# SAMV71_Xplained_Ultra_Ethernet.net
KiCad netlist of a schematic drawn in Altium Designer
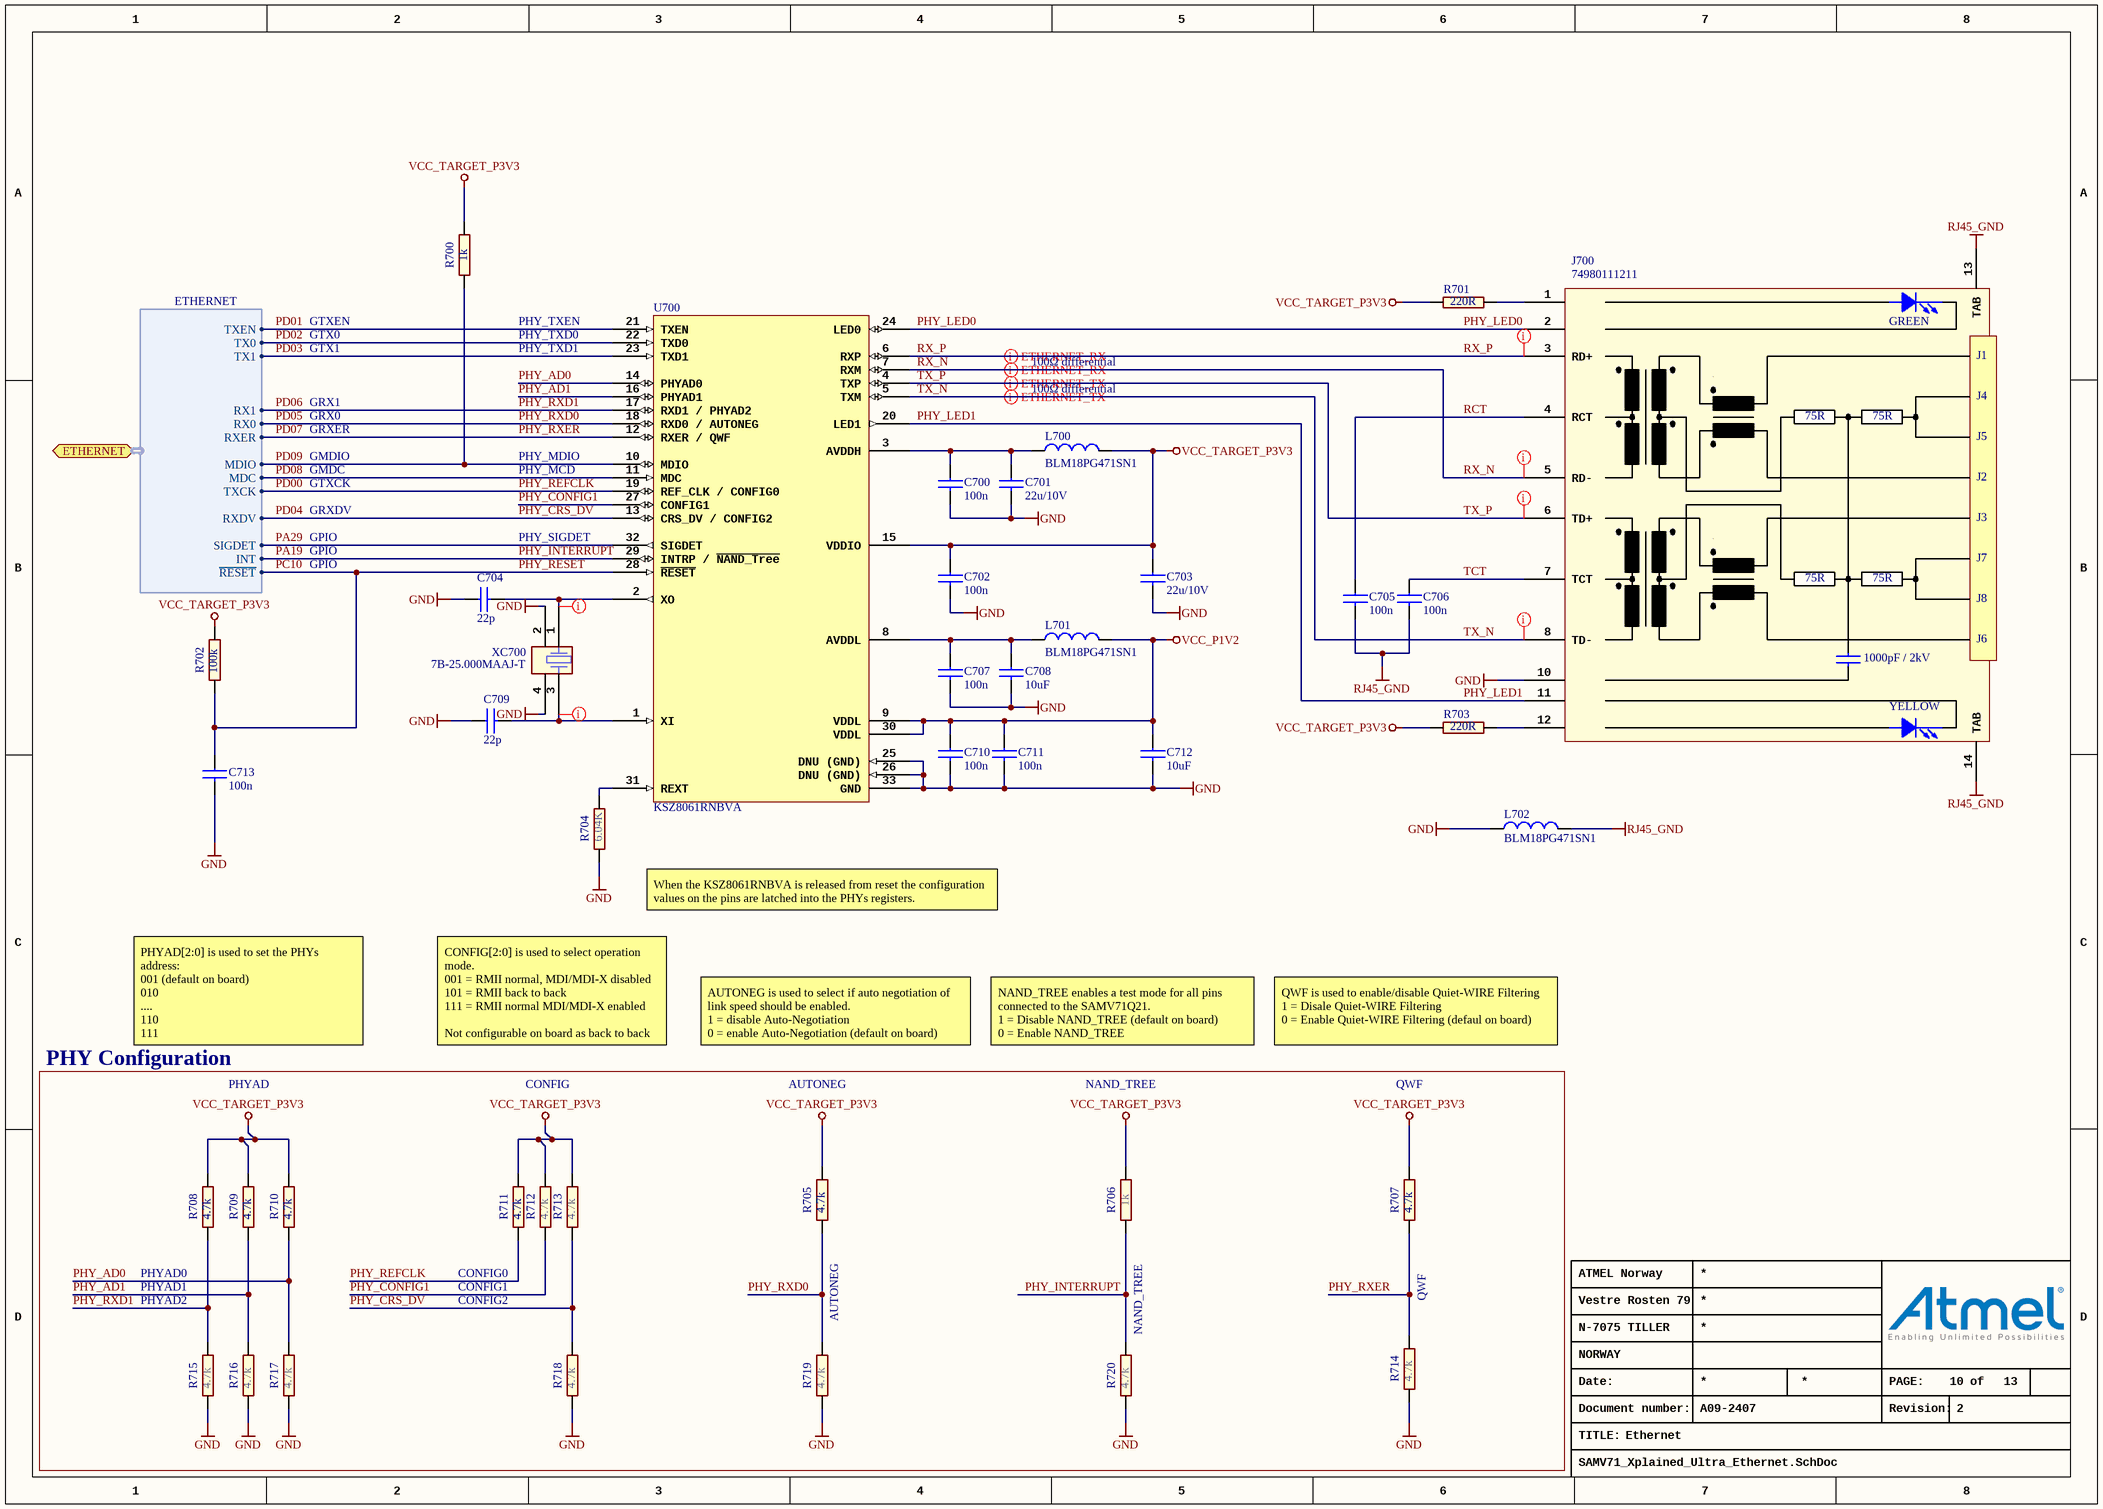
[diagram p0: SAMV71_Xplained_Ultra_Ethernet.SchDoc]

(export (version "E")
  (design (tool "Eeschema 10.0.6"))
  (components
    (comp (ref "C700")
      (value "100n")
      (footprint "AP1-00001")
      (description "Ceramic capacitor, SMD 0402, X7R, 16V, +/-10%")
      (fields (field (name "TOLERANCE") "16V, +/-10%") (field (name "MANUFACTURER") "Kemet"))
      (libsource (lib "AltiumDbLib") (part "CAP-NONPOL"))
    )
    (comp (ref "C701")
      (value "22u/10V")
      (footprint "AP1-00003")
      (description "Ceramic capacitor, SMD 0805, X5R, 10V, ±20%")
      (fields (field (name "MANUFACTURER") "tdk") (field (name "MPN") "C2012X5R1A226M/0.85"))
      (libsource (lib "AltiumDbLib") (part "CAP-NONPOL"))
    )
    (comp (ref "C702")
      (value "100n")
      (footprint "AP1-00001")
      (description "Ceramic capacitor, SMD 0402, X7R, 16V, +/-10%")
      (fields (field (name "TOLERANCE") "16V, +/-10%") (field (name "MANUFACTURER") "Kemet"))
      (libsource (lib "AltiumDbLib") (part "CAP-NONPOL"))
    )
    (comp (ref "C703")
      (value "22u/10V")
      (footprint "AP1-00003")
      (description "Ceramic capacitor, SMD 0805, X5R, 10V, ±20%")
      (fields (field (name "MANUFACTURER") "tdk") (field (name "MPN") "C2012X5R1A226M/0.85"))
      (libsource (lib "AltiumDbLib") (part "CAP-NONPOL"))
    )
    (comp (ref "C704")
      (value "22p")
      (footprint "AP1-00001")
      (description "Ceramic capacitor, SMD 0402, NP0, 50V, +/-5%")
      (fields (field (name "TOLERANCE") "50V, +/-5%") (field (name "Comment") "CAP-NONPOL"))
      (libsource (lib "AltiumDbLib") (part "CAP-NONPOL"))
    )
    (comp (ref "C705")
      (value "100n")
      (footprint "AP1-00001")
      (description "Ceramic capacitor, SMD 0402, X7R, 16V, +/-10%")
      (fields (field (name "TOLERANCE") "16V, +/-10%") (field (name "MANUFACTURER") "Kemet"))
      (libsource (lib "AltiumDbLib") (part "CAP-NONPOL"))
    )
    (comp (ref "C706")
      (value "100n")
      (footprint "AP1-00001")
      (description "Ceramic capacitor, SMD 0402, X7R, 16V, +/-10%")
      (fields (field (name "TOLERANCE") "16V, +/-10%") (field (name "MANUFACTURER") "Kemet"))
      (libsource (lib "AltiumDbLib") (part "CAP-NONPOL"))
    )
    (comp (ref "C707")
      (value "100n")
      (footprint "AP1-00001")
      (description "Ceramic capacitor, SMD 0402, X7R, 16V, +/-10%")
      (fields (field (name "TOLERANCE") "16V, +/-10%") (field (name "MANUFACTURER") "Kemet"))
      (libsource (lib "AltiumDbLib") (part "CAP-NONPOL"))
    )
    (comp (ref "C708")
      (value "10uF")
      (footprint "AP1-00041")
      (description "Ceramic capacitor, SMD 0805, X7R, 10V, 10 %, (de19441)")
      (fields (field (name "TOLERANCE") "10%") (field (name "MANUFACTURER") "Murata"))
      (libsource (lib "AltiumDbLib") (part "CAP-NONPOL"))
    )
    (comp (ref "C709")
      (value "22p")
      (footprint "AP1-00001")
      (description "Ceramic capacitor, SMD 0402, NP0, 50V, +/-5%")
      (fields (field (name "TOLERANCE") "50V, +/-5%") (field (name "Comment") "CAP-NONPOL"))
      (libsource (lib "AltiumDbLib") (part "CAP-NONPOL"))
    )
    (comp (ref "C710")
      (value "100n")
      (footprint "AP1-00001")
      (description "Ceramic capacitor, SMD 0402, X7R, 16V, +/-10%")
      (fields (field (name "TOLERANCE") "16V, +/-10%") (field (name "MANUFACTURER") "Kemet"))
      (libsource (lib "AltiumDbLib") (part "CAP-NONPOL"))
    )
    (comp (ref "C711")
      (value "100n")
      (footprint "AP1-00001")
      (description "Ceramic capacitor, SMD 0402, X7R, 16V, +/-10%")
      (fields (field (name "TOLERANCE") "16V, +/-10%") (field (name "MANUFACTURER") "Kemet"))
      (libsource (lib "AltiumDbLib") (part "CAP-NONPOL"))
    )
    (comp (ref "C712")
      (value "10uF")
      (footprint "AP1-00041")
      (description "Ceramic capacitor, SMD 0805, X7R, 10V, 10 %, (de19441)")
      (fields (field (name "TOLERANCE") "10%") (field (name "MANUFACTURER") "Murata"))
      (libsource (lib "AltiumDbLib") (part "CAP-NONPOL"))
    )
    (comp (ref "C713")
      (value "100n")
      (footprint "AP1-00001")
      (description "Ceramic capacitor, SMD 0402, X7R, 16V, +/-10%")
      (fields (field (name "TOLERANCE") "16V, +/-10%") (field (name "MANUFACTURER") "Kemet"))
      (libsource (lib "AltiumDbLib") (part "CAP-NONPOL"))
    )
    (comp (ref "J700")
      (value "74980111211")
      (footprint "AP8-00749")
      (description "10/100Base-TX, SMD, RJ45, green and yellow LEDs, integrated magnetics")
      (fields (field (name "MANUFACTURER") "Würth Elektronik") (field (name "Comment") "RJ45"))
      (libsource (lib "AltiumDbLib") (part "74980111211"))
    )
    (comp (ref "L700")
      (value "BLM18PG471SN1")
      (footprint "AP3-00005")
      (description "SMD RF inductor 0603. Z=470Ohm (@100MHz), Max R(dc)=0.65Ohm, Max current=1A")
      (fields (field (name "TOLERANCE") "±25%") (field (name "MANUFACTURER") "Murata"))
      (libsource (lib "AltiumDbLib") (part "INDUCTOR"))
    )
    (comp (ref "L701")
      (value "BLM18PG471SN1")
      (footprint "AP3-00005")
      (description "SMD RF inductor 0603. Z=470Ohm (@100MHz), Max R(dc)=0.65Ohm, Max current=1A")
      (fields (field (name "TOLERANCE") "±25%") (field (name "MANUFACTURER") "Murata"))
      (libsource (lib "AltiumDbLib") (part "INDUCTOR"))
    )
    (comp (ref "L702")
      (value "BLM18PG471SN1")
      (footprint "AP3-00005")
      (description "SMD RF inductor 0603. Z=470Ohm (@100MHz), Max R(dc)=0.65Ohm, Max current=1A")
      (fields (field (name "TOLERANCE") "±25%") (field (name "MANUFACTURER") "Murata"))
      (libsource (lib "") (part "INDUCTOR_1"))
    )
    (comp (ref "R700")
      (value "1k")
      (footprint "AP2-00000")
      (description "Thick film resistor, SMD 0402, 1/16W, 1%")
      (fields (field (name "TOLERANCE") "1 %") (field (name "Comment") "R2"))
      (libsource (lib "AltiumDbLib") (part "R2"))
    )
    (comp (ref "R701")
      (value "220R")
      (footprint "AP2-00000")
      (description "Thick film resistor, SMD 0402, 1/16W, 1%")
      (fields (field (name "TOLERANCE") "1 %") (field (name "Comment") "R2"))
      (libsource (lib "") (part "R2_3"))
    )
    (comp (ref "R702")
      (value "100k")
      (footprint "AP2-00000")
      (description "Thick film resistor, SMD 0402, 1/16W, 1%")
      (fields (field (name "TOLERANCE") "1 %") (field (name "Comment") "R2"))
      (libsource (lib "AltiumDbLib") (part "R2"))
    )
    (comp (ref "R703")
      (value "220R")
      (footprint "AP2-00000")
      (description "Thick film resistor, SMD 0402, 1/16W, 1%")
      (fields (field (name "TOLERANCE") "1 %") (field (name "Comment") "R2"))
      (libsource (lib "") (part "R2_1"))
    )
    (comp (ref "R704")
      (value "6.04K")
      (footprint "AP2-00000")
      (description "Thick film resistor, SMD 0402, 1/16W, 1%, E192")
      (fields (field (name "TOLERANCE") "1%") (field (name "Comment") "R2"))
      (libsource (lib "AltiumDbLib") (part "R2"))
    )
    (comp (ref "R705")
      (value "4.7k")
      (footprint "AP2-00000")
      (description "Thick film resistor, SMD 0402, 1/16W, 1%")
      (fields (field (name "TOLERANCE") "1 %") (field (name "Comment") "R2"))
      (libsource (lib "AltiumDbLib") (part "R2"))
    )
    (comp (ref "R706")
      (value "1k")
      (footprint "AP2-00000")
      (description "Thick film resistor, SMD 0402, 1/16W, 1%")
      (fields (field (name "TOLERANCE") "1 %") (field (name "Comment") "R2"))
      (libsource (lib "AltiumDbLib") (part "R2"))
    )
    (comp (ref "R707")
      (value "4.7k")
      (footprint "AP2-00000")
      (description "Thick film resistor, SMD 0402, 1/16W, 1%")
      (fields (field (name "TOLERANCE") "1 %") (field (name "Comment") "R2"))
      (libsource (lib "AltiumDbLib") (part "R2"))
    )
    (comp (ref "R708")
      (value "4.7k")
      (footprint "AP2-00000")
      (description "Thick film resistor, SMD 0402, 1/16W, 1%")
      (fields (field (name "TOLERANCE") "1 %") (field (name "Comment") "R2"))
      (libsource (lib "AltiumDbLib") (part "R2"))
    )
    (comp (ref "R709")
      (value "4.7k")
      (footprint "AP2-00000")
      (description "Thick film resistor, SMD 0402, 1/16W, 1%")
      (fields (field (name "TOLERANCE") "1 %") (field (name "Comment") "R2"))
      (libsource (lib "AltiumDbLib") (part "R2"))
    )
    (comp (ref "R710")
      (value "4.7k")
      (footprint "AP2-00000")
      (description "Thick film resistor, SMD 0402, 1/16W, 1%")
      (fields (field (name "TOLERANCE") "1 %") (field (name "Comment") "R2"))
      (libsource (lib "AltiumDbLib") (part "R2"))
    )
    (comp (ref "R711")
      (value "4.7k")
      (footprint "AP2-00000")
      (description "Thick film resistor, SMD 0402, 1/16W, 1%")
      (fields (field (name "TOLERANCE") "1 %") (field (name "Comment") "R2"))
      (libsource (lib "AltiumDbLib") (part "R2"))
    )
    (comp (ref "R712")
      (value "4.7k")
      (footprint "AP2-00000")
      (description "Thick film resistor, SMD 0402, 1/16W, 1%")
      (fields (field (name "TOLERANCE") "1 %") (field (name "Comment") "R2"))
      (libsource (lib "AltiumDbLib") (part "R2"))
    )
    (comp (ref "R713")
      (value "4.7k")
      (footprint "AP2-00000")
      (description "Thick film resistor, SMD 0402, 1/16W, 1%")
      (fields (field (name "TOLERANCE") "1 %") (field (name "Comment") "R2"))
      (libsource (lib "AltiumDbLib") (part "R2"))
    )
    (comp (ref "R714")
      (value "4.7k")
      (footprint "AP2-00000")
      (description "Thick film resistor, SMD 0402, 1/16W, 1%")
      (fields (field (name "TOLERANCE") "1 %") (field (name "Comment") "R2"))
      (libsource (lib "") (part "R2_2"))
    )
    (comp (ref "R715")
      (value "4.7k")
      (footprint "AP2-00000")
      (description "Thick film resistor, SMD 0402, 1/16W, 1%")
      (fields (field (name "TOLERANCE") "1 %") (field (name "Comment") "R2"))
      (libsource (lib "") (part "R2_2"))
    )
    (comp (ref "R716")
      (value "4.7k")
      (footprint "AP2-00000")
      (description "Thick film resistor, SMD 0402, 1/16W, 1%")
      (fields (field (name "TOLERANCE") "1 %") (field (name "Comment") "R2"))
      (libsource (lib "") (part "R2_2"))
    )
    (comp (ref "R717")
      (value "4.7k")
      (footprint "AP2-00000")
      (description "Thick film resistor, SMD 0402, 1/16W, 1%")
      (fields (field (name "TOLERANCE") "1 %") (field (name "Comment") "R2"))
      (libsource (lib "") (part "R2_2"))
    )
    (comp (ref "R718")
      (value "4.7k")
      (footprint "AP2-00000")
      (description "Thick film resistor, SMD 0402, 1/16W, 1%")
      (fields (field (name "TOLERANCE") "1 %") (field (name "Comment") "R2"))
      (libsource (lib "AltiumDbLib") (part "R2"))
    )
    (comp (ref "R719")
      (value "4.7k")
      (footprint "AP2-00000")
      (description "Thick film resistor, SMD 0402, 1/16W, 1%")
      (fields (field (name "TOLERANCE") "1 %") (field (name "Comment") "R2"))
      (libsource (lib "") (part "R2_2"))
    )
    (comp (ref "R720")
      (value "4.7k")
      (footprint "AP2-00000")
      (description "Thick film resistor, SMD 0402, 1/16W, 1%")
      (fields (field (name "TOLERANCE") "1 %") (field (name "Comment") "R2"))
      (libsource (lib "") (part "R2_2"))
    )
    (comp (ref "U700")
      (value "KSZ8061RNBVA")
      (footprint "AP6-00349")
      (description "10Base-T/100Base-TX PHY, RMII, EEE, 50MHz clock output, AEC-Q100 Automotive")
      (fields (field (name "Comment") "KSZ8061RNB"))
      (libsource (lib "AltiumDbLib") (part "KSZ8061RNB"))
    )
    (comp (ref "XC700")
      (value "7B-25.000MAAJ-T")
      (footprint "AP7-00067")
      (description "25.000 MHz crystal, 18pF, ±30ppm, 5.0 x 3.2 mm")
      (fields (field (name "TOLERANCE") "±30ppm") (field (name "MANUFACTURER") "TXC Corporation"))
      (libsource (lib "AltiumDbLib") (part "CRYSTAL1324"))
    )
  )
  (nets
    (net (code "2") (name "/PA19") (class "Default")
      (node (ref "R706") (pin "1") (pinfunction "1_1") (pintype "passive"))
      (node (ref "R720") (pin "1") (pinfunction "1_1") (pintype "passive"))
      (node (ref "U700") (pin "29") (pinfunction "INTRP_/_~{NAND_Tree}_29") (pintype "bidirectional"))
    )
    (net (code "3") (name "/PA29") (class "Default")
      (node (ref "U700") (pin "32") (pinfunction "SIGDET_32") (pintype "output"))
    )
    (net (code "4") (name "/PC10") (class "Default")
      (node (ref "C713") (pin "1") (pinfunction "1_1") (pintype "passive"))
      (node (ref "R702") (pin "1") (pinfunction "1_1") (pintype "passive"))
      (node (ref "U700") (pin "28") (pinfunction "~{RESET}_28") (pintype "input"))
    )
    (net (code "5") (name "/PD00") (class "Default")
      (node (ref "R711") (pin "1") (pinfunction "1_1") (pintype "passive"))
      (node (ref "U700") (pin "19") (pinfunction "REF_CLK_/_CONFIG0_19") (pintype "bidirectional"))
    )
    (net (code "6") (name "/PD01") (class "Default")
      (node (ref "U700") (pin "21") (pinfunction "TXEN_21") (pintype "input"))
    )
    (net (code "7") (name "/PD02") (class "Default")
      (node (ref "U700") (pin "22") (pinfunction "TXD0_22") (pintype "input"))
    )
    (net (code "8") (name "/PD03") (class "Default")
      (node (ref "U700") (pin "23") (pinfunction "TXD1_23") (pintype "input"))
    )
    (net (code "9") (name "/PD04") (class "Default")
      (node (ref "R713") (pin "1") (pinfunction "1_1") (pintype "passive"))
      (node (ref "R718") (pin "2") (pinfunction "2_2") (pintype "passive"))
      (node (ref "U700") (pin "13") (pinfunction "CRS_DV_/_CONFIG2_13") (pintype "bidirectional"))
    )
    (net (code "10") (name "/PD05") (class "Default")
      (node (ref "R705") (pin "1") (pinfunction "1_1") (pintype "passive"))
      (node (ref "R719") (pin "1") (pinfunction "1_1") (pintype "passive"))
      (node (ref "U700") (pin "18") (pinfunction "RXD0_/_AUTONEG_18") (pintype "bidirectional"))
    )
    (net (code "11") (name "/PD06") (class "Default")
      (node (ref "R708") (pin "1") (pinfunction "1_1") (pintype "passive"))
      (node (ref "R715") (pin "1") (pinfunction "1_1") (pintype "passive"))
      (node (ref "U700") (pin "17") (pinfunction "RXD1_/_PHYAD2_17") (pintype "bidirectional"))
    )
    (net (code "12") (name "/PD07") (class "Default")
      (node (ref "R707") (pin "1") (pinfunction "1_1") (pintype "passive"))
      (node (ref "R714") (pin "1") (pinfunction "1_1") (pintype "passive"))
      (node (ref "U700") (pin "12") (pinfunction "RXER_/_QWF_12") (pintype "bidirectional"))
    )
    (net (code "13") (name "/PD08") (class "Default")
      (node (ref "U700") (pin "11") (pinfunction "MDC_11") (pintype "input"))
    )
    (net (code "14") (name "/PD09") (class "Default")
      (node (ref "R700") (pin "1") (pinfunction "1_1") (pintype "passive"))
      (node (ref "U700") (pin "10") (pinfunction "MDIO_10") (pintype "bidirectional"))
    )
    (net (code "15") (name "/PHY_AD0") (class "Default")
      (node (ref "R710") (pin "1") (pinfunction "1_1") (pintype "passive"))
      (node (ref "R717") (pin "1") (pinfunction "1_1") (pintype "passive"))
      (node (ref "U700") (pin "14") (pinfunction "PHYAD0_14") (pintype "bidirectional"))
    )
    (net (code "16") (name "/PHY_AD1") (class "Default")
      (node (ref "R709") (pin "1") (pinfunction "1_1") (pintype "passive"))
      (node (ref "R716") (pin "1") (pinfunction "1_1") (pintype "passive"))
      (node (ref "U700") (pin "16") (pinfunction "PHYAD1_16") (pintype "bidirectional"))
    )
    (net (code "17") (name "/PHY_CONFIG1") (class "Default")
      (node (ref "R712") (pin "1") (pinfunction "1_1") (pintype "passive"))
      (node (ref "U700") (pin "27") (pinfunction "CONFIG1_27") (pintype "bidirectional"))
    )
    (net (code "18") (name "/PHY_LED0") (class "Default")
      (node (ref "J700") (pin "2") (pintype "passive"))
      (node (ref "U700") (pin "24") (pinfunction "LED0_24") (pintype "bidirectional"))
    )
    (net (code "19") (name "/PHY_LED1") (class "Default")
      (node (ref "J700") (pin "11") (pintype "passive"))
      (node (ref "U700") (pin "20") (pinfunction "LED1_20") (pintype "output"))
    )
    (net (code "20") (name "/RCT") (class "Default")
      (node (ref "C705") (pin "1") (pinfunction "1_1") (pintype "passive"))
      (node (ref "J700") (pin "4") (pinfunction "RCT_4") (pintype "passive"))
    )
    (net (code "21") (name "/RX_N") (class "Default")
      (node (ref "J700") (pin "5") (pinfunction "RD-_5") (pintype "passive"))
      (node (ref "U700") (pin "7") (pinfunction "RXM_7") (pintype "bidirectional"))
    )
    (net (code "22") (name "/RX_P") (class "Default")
      (node (ref "J700") (pin "3") (pinfunction "RD+_3") (pintype "passive"))
      (node (ref "U700") (pin "6") (pinfunction "RXP_6") (pintype "bidirectional"))
    )
    (net (code "23") (name "/TCT") (class "Default")
      (node (ref "C706") (pin "1") (pinfunction "1_1") (pintype "passive"))
      (node (ref "J700") (pin "7") (pinfunction "TCT_7") (pintype "passive"))
    )
    (net (code "24") (name "/TX_N") (class "Default")
      (node (ref "J700") (pin "8") (pinfunction "TD-_8") (pintype "passive"))
      (node (ref "U700") (pin "5") (pinfunction "TXM_5") (pintype "bidirectional"))
    )
    (net (code "25") (name "/TX_P") (class "Default")
      (node (ref "J700") (pin "6") (pinfunction "TD+_6") (pintype "passive"))
      (node (ref "U700") (pin "4") (pinfunction "TXP_4") (pintype "bidirectional"))
    )
    (net (code "27") (name "GND") (class "Default")
      (node (ref "C700") (pin "2") (pinfunction "2_2") (pintype "passive"))
      (node (ref "C701") (pin "2") (pinfunction "2_2") (pintype "passive"))
      (node (ref "C702") (pin "2") (pinfunction "2_2") (pintype "passive"))
      (node (ref "C703") (pin "2") (pinfunction "2_2") (pintype "passive"))
      (node (ref "C704") (pin "1") (pinfunction "1_1") (pintype "passive"))
      (node (ref "C707") (pin "2") (pinfunction "2_2") (pintype "passive"))
      (node (ref "C708") (pin "2") (pinfunction "2_2") (pintype "passive"))
      (node (ref "C709") (pin "1") (pinfunction "1_1") (pintype "passive"))
      (node (ref "C710") (pin "2") (pinfunction "2_2") (pintype "passive"))
      (node (ref "C711") (pin "2") (pinfunction "2_2") (pintype "passive"))
      (node (ref "C712") (pin "2") (pinfunction "2_2") (pintype "passive"))
      (node (ref "C713") (pin "2") (pinfunction "2_2") (pintype "passive"))
      (node (ref "J700") (pin "10") (pintype "passive"))
      (node (ref "L702") (pin "1") (pinfunction "1_1") (pintype "passive"))
      (node (ref "R704") (pin "1") (pinfunction "1_1") (pintype "passive"))
      (node (ref "R714") (pin "2") (pinfunction "2_2") (pintype "passive"))
      (node (ref "R715") (pin "2") (pinfunction "2_2") (pintype "passive"))
      (node (ref "R716") (pin "2") (pinfunction "2_2") (pintype "passive"))
      (node (ref "R717") (pin "2") (pinfunction "2_2") (pintype "passive"))
      (node (ref "R718") (pin "1") (pinfunction "1_1") (pintype "passive"))
      (node (ref "R719") (pin "2") (pinfunction "2_2") (pintype "passive"))
      (node (ref "R720") (pin "2") (pinfunction "2_2") (pintype "passive"))
      (node (ref "U700") (pin "25") (pinfunction "DNU_(GND)_25") (pintype "input"))
      (node (ref "U700") (pin "26") (pinfunction "DNU_(GND)_26") (pintype "input"))
      (node (ref "U700") (pin "33") (pinfunction "GND_33") (pintype "power_in"))
      (node (ref "XC700") (pin "2") (pinfunction "2_2") (pintype "passive"))
      (node (ref "XC700") (pin "4") (pinfunction "4_4") (pintype "passive"))
    )
    (net (code "28") (name "Net-(J700-Pad1)") (class "Default")
      (node (ref "J700") (pin "1") (pintype "passive"))
      (node (ref "R701") (pin "1") (pinfunction "1_1") (pintype "passive"))
    )
    (net (code "29") (name "Net-(J700-Pad12)") (class "Default")
      (node (ref "J700") (pin "12") (pintype "passive"))
      (node (ref "R703") (pin "2") (pinfunction "2_2") (pintype "passive"))
    )
    (net (code "30") (name "Net-(U700-AVDDH)") (class "Default")
      (node (ref "C700") (pin "1") (pinfunction "1_1") (pintype "passive"))
      (node (ref "C701") (pin "1") (pinfunction "1_1") (pintype "passive"))
      (node (ref "L700") (pin "2") (pinfunction "2_2") (pintype "passive"))
      (node (ref "U700") (pin "3") (pinfunction "AVDDH_3") (pintype "power_in"))
    )
    (net (code "31") (name "Net-(U700-AVDDL)") (class "Default")
      (node (ref "C707") (pin "1") (pinfunction "1_1") (pintype "passive"))
      (node (ref "C708") (pin "1") (pinfunction "1_1") (pintype "passive"))
      (node (ref "L701") (pin "2") (pinfunction "2_2") (pintype "passive"))
      (node (ref "U700") (pin "8") (pinfunction "AVDDL_8") (pintype "power_in"))
    )
    (net (code "32") (name "Net-(U700-REXT)") (class "Default")
      (node (ref "R704") (pin "2") (pinfunction "2_2") (pintype "passive"))
      (node (ref "U700") (pin "31") (pinfunction "REXT_31") (pintype "input"))
    )
    (net (code "33") (name "Net-(U700-XI)") (class "Default")
      (node (ref "C709") (pin "2") (pinfunction "2_2") (pintype "passive"))
      (node (ref "U700") (pin "1") (pinfunction "XI_1") (pintype "input"))
      (node (ref "XC700") (pin "3") (pinfunction "3_3") (pintype "passive"))
    )
    (net (code "34") (name "Net-(U700-XO)") (class "Default")
      (node (ref "C704") (pin "2") (pinfunction "2_2") (pintype "passive"))
      (node (ref "U700") (pin "2") (pinfunction "XO_2") (pintype "output"))
      (node (ref "XC700") (pin "1") (pinfunction "1_1") (pintype "passive"))
    )
    (net (code "35") (name "RJ45_GND") (class "Default")
      (node (ref "C705") (pin "2") (pinfunction "2_2") (pintype "passive"))
      (node (ref "C706") (pin "2") (pinfunction "2_2") (pintype "passive"))
      (node (ref "J700") (pin "13") (pinfunction "TAB_13") (pintype "power_in"))
      (node (ref "J700") (pin "14") (pinfunction "TAB_14") (pintype "power_in"))
      (node (ref "L702") (pin "2") (pinfunction "2_2") (pintype "passive"))
    )
    (net (code "36") (name "VCC_P1V2") (class "Default")
      (node (ref "C710") (pin "1") (pinfunction "1_1") (pintype "passive"))
      (node (ref "C711") (pin "1") (pinfunction "1_1") (pintype "passive"))
      (node (ref "C712") (pin "1") (pinfunction "1_1") (pintype "passive"))
      (node (ref "L701") (pin "1") (pinfunction "1_1") (pintype "passive"))
      (node (ref "U700") (pin "30") (pinfunction "VDDL_30") (pintype "power_in"))
      (node (ref "U700") (pin "9") (pinfunction "VDDL_9") (pintype "power_in"))
    )
    (net (code "37") (name "VCC_TARGET_P3V3") (class "Default")
      (node (ref "C702") (pin "1") (pinfunction "1_1") (pintype "passive"))
      (node (ref "C703") (pin "1") (pinfunction "1_1") (pintype "passive"))
      (node (ref "L700") (pin "1") (pinfunction "1_1") (pintype "passive"))
      (node (ref "R700") (pin "2") (pinfunction "2_2") (pintype "passive"))
      (node (ref "R701") (pin "2") (pinfunction "2_2") (pintype "passive"))
      (node (ref "R702") (pin "2") (pinfunction "2_2") (pintype "passive"))
      (node (ref "R703") (pin "1") (pinfunction "1_1") (pintype "passive"))
      (node (ref "R705") (pin "2") (pinfunction "2_2") (pintype "passive"))
      (node (ref "R706") (pin "2") (pinfunction "2_2") (pintype "passive"))
      (node (ref "R707") (pin "2") (pinfunction "2_2") (pintype "passive"))
      (node (ref "R708") (pin "2") (pinfunction "2_2") (pintype "passive"))
      (node (ref "R709") (pin "2") (pinfunction "2_2") (pintype "passive"))
      (node (ref "R710") (pin "2") (pinfunction "2_2") (pintype "passive"))
      (node (ref "R711") (pin "2") (pinfunction "2_2") (pintype "passive"))
      (node (ref "R712") (pin "2") (pinfunction "2_2") (pintype "passive"))
      (node (ref "R713") (pin "2") (pinfunction "2_2") (pintype "passive"))
      (node (ref "U700") (pin "15") (pinfunction "VDDIO_15") (pintype "power_in"))
    )
  )
)
